# SCH_CLASS_ESP32-S2-MAIN_2024-03-08.net
KiCad netlist of a schematic drawn in EasyEDA
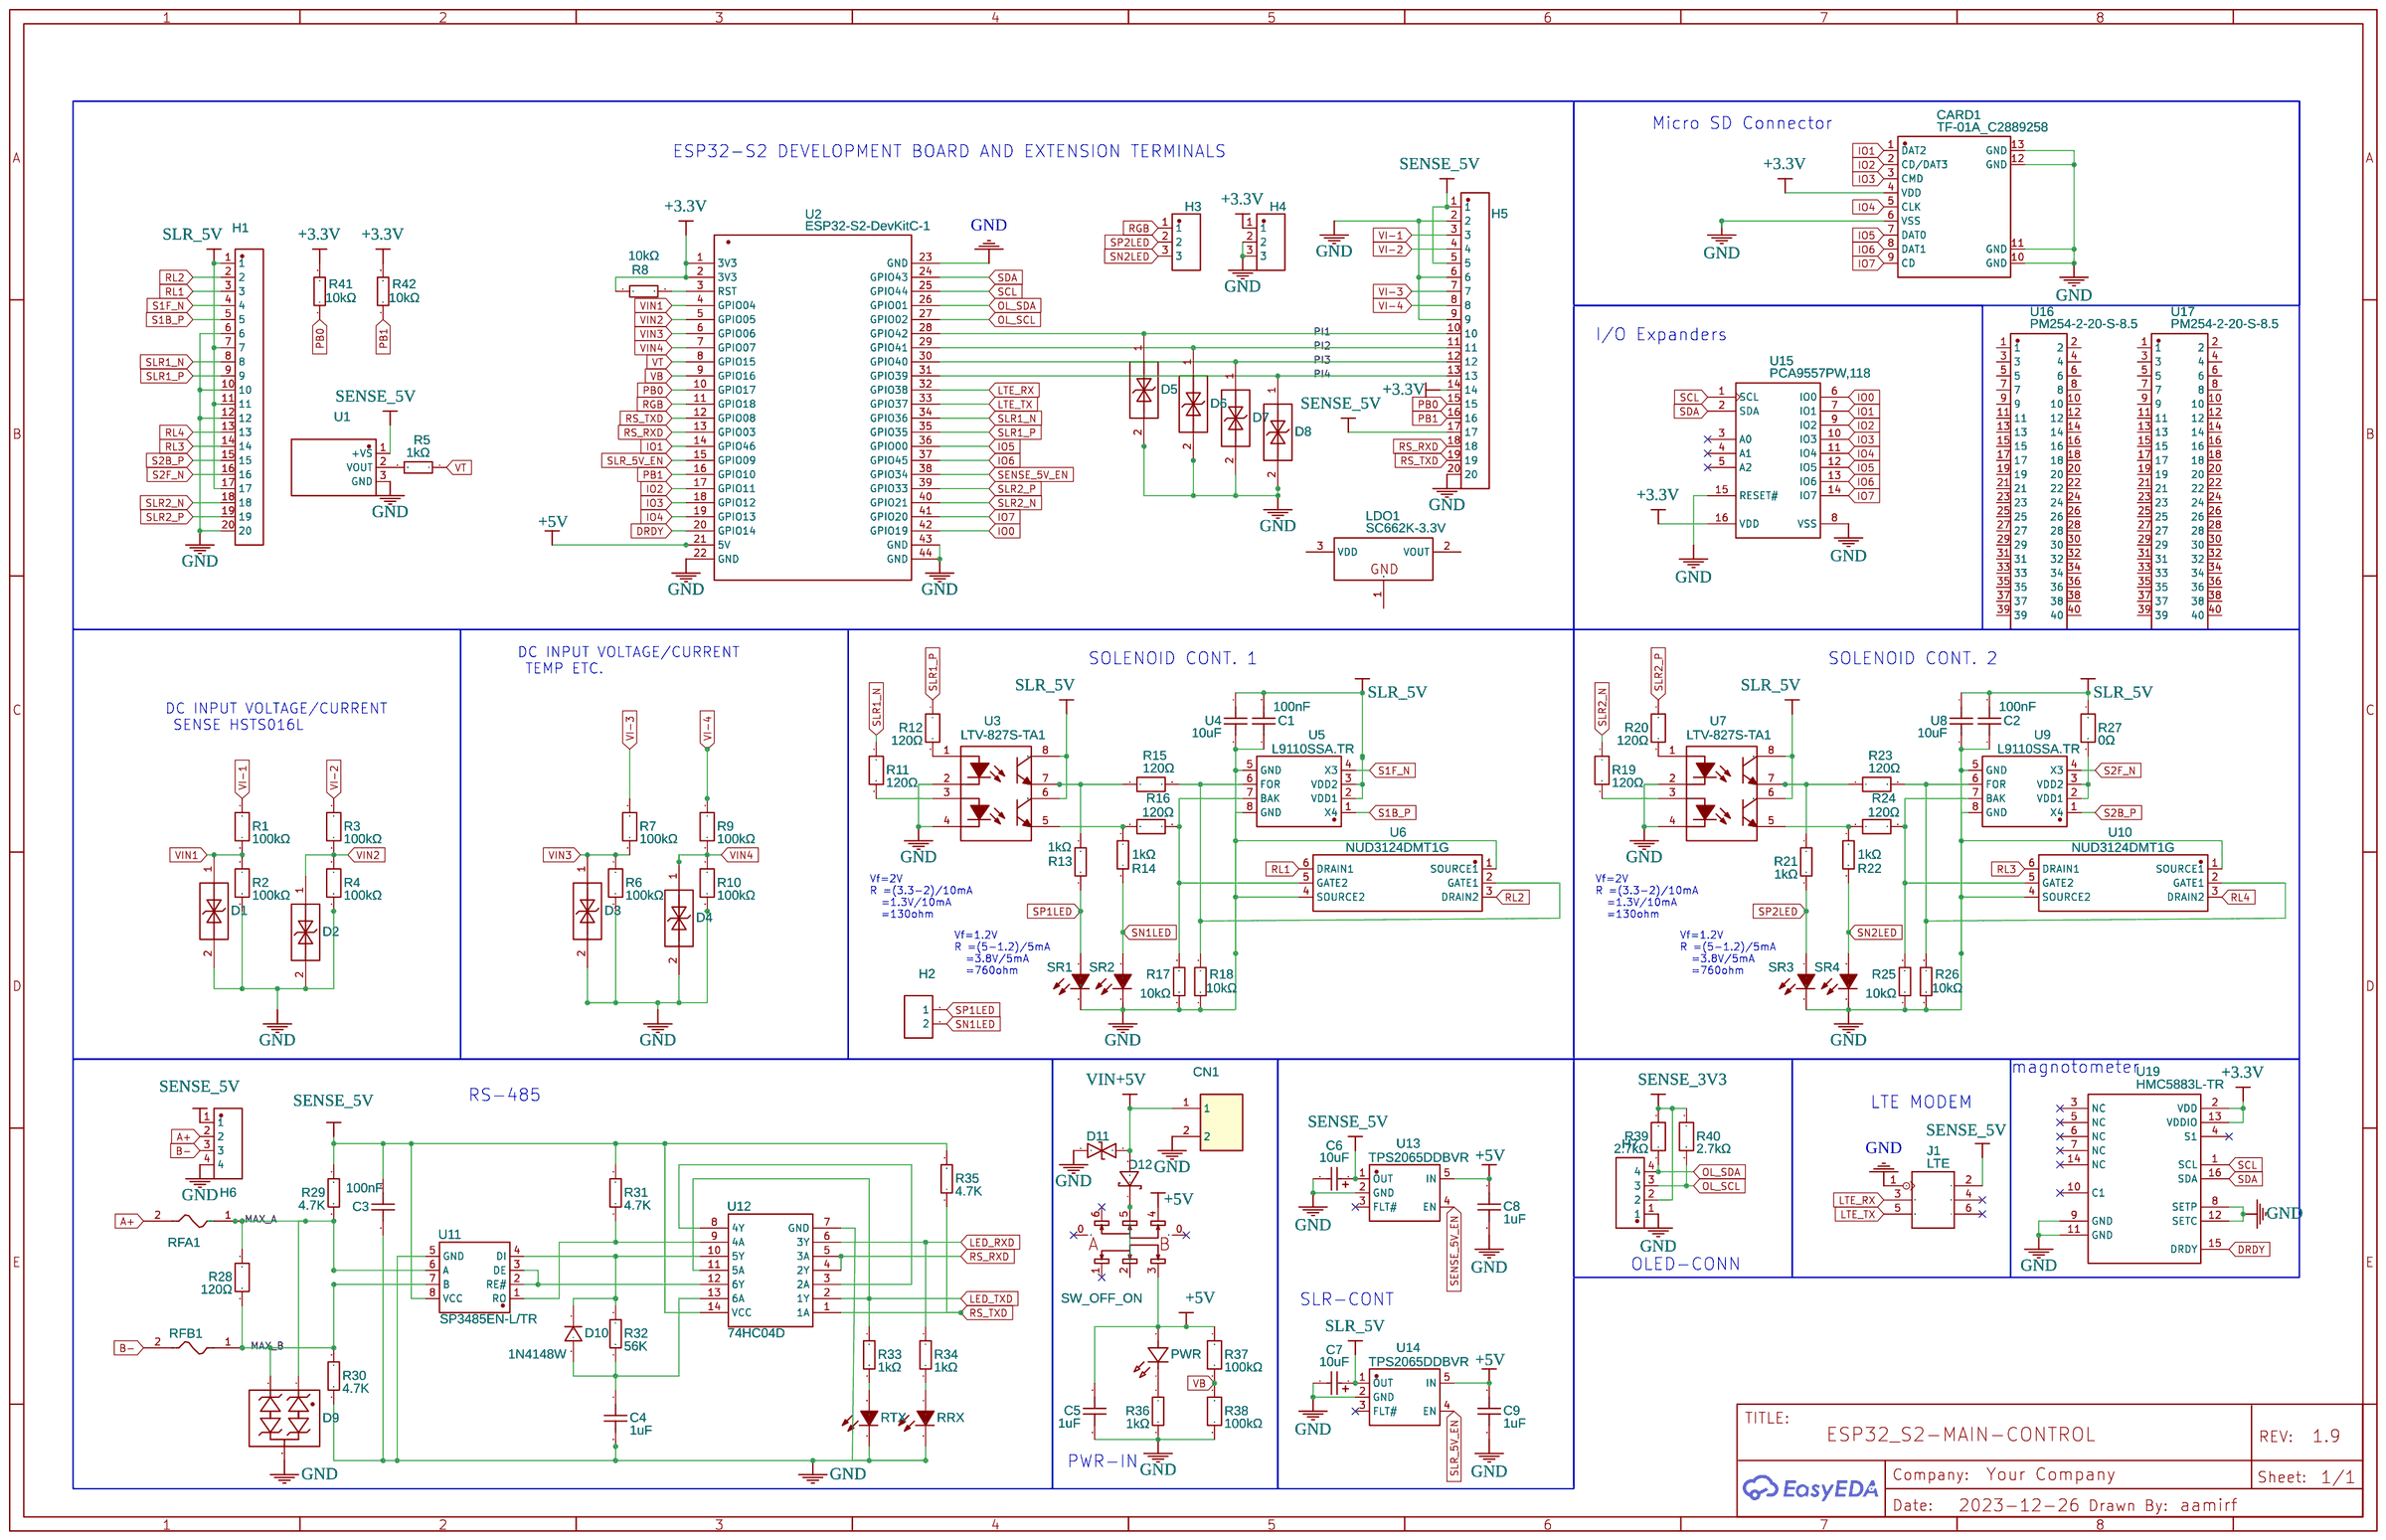
[diagram p0: schematic sheet]

(export (version "E")
  (design (tool "Eeschema 10.0.6"))
  (components
    (comp (ref "C1")
      (value "100nF")
      (fields (field (name "Manufacturer Part") "C1005X5R0J104K050BA") (field (name "Manufacturer") "TDK"))
      (libsource (lib "") (part "C1005X5R0J104K050BA"))
    )
    (comp (ref "C2")
      (value "100nF")
      (fields (field (name "Manufacturer Part") "C1005X5R0J104K050BA") (field (name "Manufacturer") "TDK"))
      (libsource (lib "") (part "C1005X5R0J104K050BA"))
    )
    (comp (ref "C3")
      (value "100nF")
      (fields (field (name "Manufacturer Part") "C1005X5R0J104K050BA") (field (name "Manufacturer") "TDK"))
      (libsource (lib "") (part "C1005X5R0J104K050BA_1"))
    )
    (comp (ref "C4")
      (value "1uF")
      (fields
        (field (name "Manufacturer Part") "GRM155R61H105ME05D")
        (field (name "Manufacturer") "muRata(村田)")
      )
      (libsource (lib "") (part "GRM155R61H105ME05D"))
    )
    (comp (ref "C5")
      (value "1uF")
      (fields
        (field (name "Manufacturer Part") "GRM155R61H105ME05D")
        (field (name "Manufacturer") "muRata(村田)")
      )
      (libsource (lib "") (part "GRM155R61H105ME05D_1"))
    )
    (comp (ref "C6")
      (value "10uF")
      (fields
        (field (name "Manufacturer Part") "CA45A-A-16V-10uF-K")
        (field (name "Manufacturer") "CEC(振华新云)")
      )
      (libsource (lib "") (part "CA45A-A-16V-10UF-K"))
    )
    (comp (ref "C7")
      (value "10uF")
      (fields
        (field (name "Manufacturer Part") "CA45A-A-16V-10uF-K")
        (field (name "Manufacturer") "CEC(振华新云)")
      )
      (libsource (lib "") (part "CA45A-A-16V-10UF-K"))
    )
    (comp (ref "C8")
      (value "1uF")
      (fields
        (field (name "Manufacturer Part") "GRM155R61H105ME05D")
        (field (name "Manufacturer") "muRata(村田)")
      )
      (libsource (lib "") (part "GRM155R61H105ME05D"))
    )
    (comp (ref "C9")
      (value "1uF")
      (fields
        (field (name "Manufacturer Part") "GRM155R61H105ME05D")
        (field (name "Manufacturer") "muRata(村田)")
      )
      (libsource (lib "") (part "GRM155R61H105ME05D"))
    )
    (comp (ref "CARD1")
      (value "TF-01A_C2889258")
      (fields (field (name "Manufacturer Part") "TF-01A") (field (name "Manufacturer") "Yuandi(台湾元迪)"))
      (libsource (lib "") (part "TF-01A_C2889258"))
    )
    (comp (ref "CN1")
      (value "B2B-PH-K-S(LF)(SN)")
      (fields (field (name "Manufacturer") "JST"))
      (libsource (lib "") (part "B2B-PH-K-S(LF)(SN)"))
    )
    (comp (ref "D1")
      (value "KESD5311X")
      (fields (field (name "Manufacturer") "KUU"))
      (libsource (lib "") (part "KESD5311X"))
    )
    (comp (ref "D2")
      (value "KESD5311X")
      (fields (field (name "Manufacturer") "KUU"))
      (libsource (lib "") (part "KESD5311X"))
    )
    (comp (ref "D3")
      (value "KESD5311X")
      (fields (field (name "Manufacturer") "KUU"))
      (libsource (lib "") (part "KESD5311X"))
    )
    (comp (ref "D4")
      (value "KESD5311X")
      (fields (field (name "Manufacturer") "KUU"))
      (libsource (lib "") (part "KESD5311X"))
    )
    (comp (ref "D5")
      (value "KESD5311X")
      (fields (field (name "Manufacturer") "KUU"))
      (libsource (lib "") (part "KESD5311X"))
    )
    (comp (ref "D6")
      (value "KESD5311X")
      (fields (field (name "Manufacturer") "KUU"))
      (libsource (lib "") (part "KESD5311X"))
    )
    (comp (ref "D7")
      (value "KESD5311X")
      (fields (field (name "Manufacturer") "KUU"))
      (libsource (lib "") (part "KESD5311X"))
    )
    (comp (ref "D8")
      (value "KESD5311X")
      (fields (field (name "Manufacturer") "KUU"))
      (libsource (lib "") (part "KESD5311X"))
    )
    (comp (ref "D9")
      (value "SM712_C502564")
      (fields (field (name "Manufacturer Part") "SM712") (field (name "Manufacturer") "MDD"))
      (libsource (lib "") (part "SM712_C502564"))
    )
    (comp (ref "D10")
      (value "1N4148W")
      (fields (field (name "Manufacturer") "SEMTECH"))
      (libsource (lib "") (part "1N4148W_C81598"))
    )
    (comp (ref "D11")
      (value "LESD5D5.0CT1G")
      (fields (field (name "Manufacturer") "LRC(乐山无线电)"))
      (libsource (lib "") (part "LESD5D5.0CT1G"))
    )
    (comp (ref "D12")
      (value "BAT760-7")
      (fields (field (name "Manufacturer") "DIODES(美台)"))
      (libsource (lib "") (part "BAT760-7"))
    )
    (comp (ref "H1")
      (value "KH-2.54PH180-1X20P-L11.5")
      (fields (field (name "Manufacturer") "kinghelm(金航标)"))
      (libsource (lib "") (part "KH-2.54PH180-1X20P-L11.5"))
    )
    (comp (ref "H2") (value "HDR-F-2.54_1x2") (libsource (lib "") (part "HDR-F-2.54_1x2")))
    (comp (ref "H3")
      (value "KH-2.54PH180-1X3P-L11.5")
      (fields (field (name "Manufacturer") "kinghelm(金航标)"))
      (libsource (lib "") (part "KH-2.54PH180-1X3P-L11.5"))
    )
    (comp (ref "H4")
      (value "KH-2.54PH180-1X3P-L11.5")
      (fields (field (name "Manufacturer") "kinghelm(金航标)"))
      (libsource (lib "") (part "KH-2.54PH180-1X3P-L11.5"))
    )
    (comp (ref "H5")
      (value "KH-2.54PH180-1X20P-L11.5")
      (fields (field (name "Manufacturer") "kinghelm(金航标)"))
      (libsource (lib "") (part "KH-2.54PH180-1X20P-L11.5"))
    )
    (comp (ref "H6")
      (value "X6511WV-04H-C30D60")
      (fields (field (name "Manufacturer") "XKB Connectivity(中国星坤)"))
      (libsource (lib "") (part "X6511WV-04H-C30D60"))
    )
    (comp (ref "H7")
      (value "X6511WV-04H-C30D60")
      (fields (field (name "Manufacturer") "XKB Connectivity(中国星坤)"))
      (libsource (lib "") (part "X6511WV-04H-C30D60_1"))
    )
    (comp (ref "J1") (value "LTE") (libsource (lib "") (part "MALE-HEADER(2X3P-2.54)")))
    (comp (ref "LDO1")
      (value "SC662K-3.3V")
      (fields (field (name "Manufacturer") "FM(富满)"))
      (libsource (lib "") (part "SC662K-3.3V"))
    )
    (comp (ref "PWR")
      (value "16-213/BHC-ZL1M2B6Y/3T")
      (fields (field (name "Manufacturer") "EVERLIGHT(亿光)"))
      (libsource (lib "") (part "16-213/BHC-ZL1M2B6Y/3T"))
    )
    (comp (ref "R1")
      (value "100kΩ")
      (fields
        (field (name "Manufacturer Part") "CQ02WGJ0104TCE")
        (field (name "Manufacturer") "UNI-ROYAL(厚声)")
      )
      (libsource (lib "") (part "CQ02WGJ0104TCE"))
    )
    (comp (ref "R2")
      (value "100kΩ")
      (fields
        (field (name "Manufacturer Part") "CQ02WGJ0104TCE")
        (field (name "Manufacturer") "UNI-ROYAL(厚声)")
      )
      (libsource (lib "") (part "CQ02WGJ0104TCE"))
    )
    (comp (ref "R3")
      (value "100kΩ")
      (fields
        (field (name "Manufacturer Part") "CQ02WGJ0104TCE")
        (field (name "Manufacturer") "UNI-ROYAL(厚声)")
      )
      (libsource (lib "") (part "CQ02WGJ0104TCE"))
    )
    (comp (ref "R4")
      (value "100kΩ")
      (fields
        (field (name "Manufacturer Part") "CQ02WGJ0104TCE")
        (field (name "Manufacturer") "UNI-ROYAL(厚声)")
      )
      (libsource (lib "") (part "CQ02WGJ0104TCE"))
    )
    (comp (ref "R5")
      (value "1kΩ")
      (fields (field (name "Manufacturer Part") "AR02DTD1001") (field (name "Manufacturer") "Viking(光颉)"))
      (libsource (lib "") (part "AR02DTD1001"))
    )
    (comp (ref "R6")
      (value "100kΩ")
      (fields
        (field (name "Manufacturer Part") "CQ02WGJ0104TCE")
        (field (name "Manufacturer") "UNI-ROYAL(厚声)")
      )
      (libsource (lib "") (part "CQ02WGJ0104TCE"))
    )
    (comp (ref "R7")
      (value "100kΩ")
      (fields
        (field (name "Manufacturer Part") "CQ02WGJ0104TCE")
        (field (name "Manufacturer") "UNI-ROYAL(厚声)")
      )
      (libsource (lib "") (part "CQ02WGJ0104TCE"))
    )
    (comp (ref "R8")
      (value "10kΩ")
      (fields
        (field (name "Manufacturer Part") "0402WGF1002TCE")
        (field (name "Manufacturer") "UNI-ROYAL(厚声)")
      )
      (libsource (lib "") (part "0402WGF1002TCE_1"))
    )
    (comp (ref "R9")
      (value "100kΩ")
      (fields
        (field (name "Manufacturer Part") "CQ02WGJ0104TCE")
        (field (name "Manufacturer") "UNI-ROYAL(厚声)")
      )
      (libsource (lib "") (part "CQ02WGJ0104TCE"))
    )
    (comp (ref "R10")
      (value "100kΩ")
      (fields
        (field (name "Manufacturer Part") "CQ02WGJ0104TCE")
        (field (name "Manufacturer") "UNI-ROYAL(厚声)")
      )
      (libsource (lib "") (part "CQ02WGJ0104TCE"))
    )
    (comp (ref "R11")
      (value "120Ω")
      (fields (field (name "Manufacturer Part") "RM04FTN1200") (field (name "Manufacturer") "大毅科技"))
      (libsource (lib "") (part "RM04FTN1200"))
    )
    (comp (ref "R12")
      (value "120Ω")
      (fields (field (name "Manufacturer Part") "RM04FTN1200") (field (name "Manufacturer") "大毅科技"))
      (libsource (lib "") (part "RM04FTN1200"))
    )
    (comp (ref "R13")
      (value "1kΩ")
      (fields (field (name "Manufacturer Part") "AR02DTD1001") (field (name "Manufacturer") "Viking(光颉)"))
      (libsource (lib "") (part "AR02DTD1001_1"))
    )
    (comp (ref "R14")
      (value "1kΩ")
      (fields (field (name "Manufacturer Part") "AR02DTD1001") (field (name "Manufacturer") "Viking(光颉)"))
      (libsource (lib "") (part "AR02DTD1001_1"))
    )
    (comp (ref "R15")
      (value "120Ω")
      (fields (field (name "Manufacturer Part") "RM04FTN1200") (field (name "Manufacturer") "大毅科技"))
      (libsource (lib "") (part "RM04FTN1200_1"))
    )
    (comp (ref "R16")
      (value "120Ω")
      (fields (field (name "Manufacturer Part") "RM04FTN1200") (field (name "Manufacturer") "大毅科技"))
      (libsource (lib "") (part "RM04FTN1200_1"))
    )
    (comp (ref "R17")
      (value "10kΩ")
      (fields
        (field (name "Manufacturer Part") "0402WGF1002TCE")
        (field (name "Manufacturer") "UNI-ROYAL(厚声)")
      )
      (libsource (lib "") (part "0402WGF1002TCE"))
    )
    (comp (ref "R18")
      (value "10kΩ")
      (fields
        (field (name "Manufacturer Part") "0402WGF1002TCE")
        (field (name "Manufacturer") "UNI-ROYAL(厚声)")
      )
      (libsource (lib "") (part "0402WGF1002TCE"))
    )
    (comp (ref "R19")
      (value "120Ω")
      (fields (field (name "Manufacturer Part") "RM04FTN1200") (field (name "Manufacturer") "大毅科技"))
      (libsource (lib "") (part "RM04FTN1200"))
    )
    (comp (ref "R20")
      (value "120Ω")
      (fields (field (name "Manufacturer Part") "RM04FTN1200") (field (name "Manufacturer") "大毅科技"))
      (libsource (lib "") (part "RM04FTN1200"))
    )
    (comp (ref "R21")
      (value "1kΩ")
      (fields (field (name "Manufacturer Part") "AR02DTD1001") (field (name "Manufacturer") "Viking(光颉)"))
      (libsource (lib "") (part "AR02DTD1001_1"))
    )
    (comp (ref "R22")
      (value "1kΩ")
      (fields (field (name "Manufacturer Part") "AR02DTD1001") (field (name "Manufacturer") "Viking(光颉)"))
      (libsource (lib "") (part "AR02DTD1001_1"))
    )
    (comp (ref "R23")
      (value "120Ω")
      (fields (field (name "Manufacturer Part") "RM04FTN1200") (field (name "Manufacturer") "大毅科技"))
      (libsource (lib "") (part "RM04FTN1200_1"))
    )
    (comp (ref "R24")
      (value "120Ω")
      (fields (field (name "Manufacturer Part") "RM04FTN1200") (field (name "Manufacturer") "大毅科技"))
      (libsource (lib "") (part "RM04FTN1200_1"))
    )
    (comp (ref "R25")
      (value "10kΩ")
      (fields
        (field (name "Manufacturer Part") "0402WGF1002TCE")
        (field (name "Manufacturer") "UNI-ROYAL(厚声)")
      )
      (libsource (lib "") (part "0402WGF1002TCE"))
    )
    (comp (ref "R26")
      (value "10kΩ")
      (fields
        (field (name "Manufacturer Part") "0402WGF1002TCE")
        (field (name "Manufacturer") "UNI-ROYAL(厚声)")
      )
      (libsource (lib "") (part "0402WGF1002TCE"))
    )
    (comp (ref "R27")
      (value "0Ω")
      (fields (field (name "Manufacturer Part") "CR-03JA7----0R") (field (name "Manufacturer") "Viking(光颉)"))
      (libsource (lib "") (part "CR-03JA7----0R"))
    )
    (comp (ref "R28")
      (value "120Ω")
      (fields (field (name "Manufacturer Part") "FRC0603J121 TS") (field (name "Manufacturer") "FOJAN(富捷)"))
      (libsource (lib "") (part "FRC0603J121 TS"))
    )
    (comp (ref "R29")
      (value "4.7K")
      (fields (field (name "Manufacturer Part") "0603WAF4701T5E") (field (name "Manufacturer") "UniOhm"))
      (libsource (lib "") (part "0603WAF4701T5E"))
    )
    (comp (ref "R30")
      (value "4.7K")
      (fields (field (name "Manufacturer Part") "0603WAF4701T5E") (field (name "Manufacturer") "UniOhm"))
      (libsource (lib "") (part "0603WAF4701T5E"))
    )
    (comp (ref "R31")
      (value "4.7K")
      (fields (field (name "Manufacturer Part") "0603WAF4701T5E") (field (name "Manufacturer") "UniOhm"))
      (libsource (lib "") (part "0603WAF4701T5E"))
    )
    (comp (ref "R32")
      (value "56K")
      (fields (field (name "Manufacturer Part") "0603WAF5602T5E") (field (name "Manufacturer") "UniOhm"))
      (libsource (lib "") (part "0603WAF5602T5E"))
    )
    (comp (ref "R33")
      (value "1kΩ")
      (fields (field (name "Manufacturer Part") "AR02DTD1001") (field (name "Manufacturer") "Viking(光颉)"))
      (libsource (lib "") (part "AR02DTD1001_1"))
    )
    (comp (ref "R34")
      (value "1kΩ")
      (fields (field (name "Manufacturer Part") "AR02DTD1001") (field (name "Manufacturer") "Viking(光颉)"))
      (libsource (lib "") (part "AR02DTD1001_1"))
    )
    (comp (ref "R35")
      (value "4.7K")
      (fields (field (name "Manufacturer Part") "0603WAF4701T5E") (field (name "Manufacturer") "UniOhm"))
      (libsource (lib "") (part "0603WAF4701T5E"))
    )
    (comp (ref "R36")
      (value "1kΩ")
      (fields (field (name "Manufacturer Part") "AR02DTD1001") (field (name "Manufacturer") "Viking(光颉)"))
      (libsource (lib "") (part "AR02DTD1001_1"))
    )
    (comp (ref "R37")
      (value "100kΩ")
      (fields
        (field (name "Manufacturer Part") "CQ02WGJ0104TCE")
        (field (name "Manufacturer") "UNI-ROYAL(厚声)")
      )
      (libsource (lib "") (part "CQ02WGJ0104TCE"))
    )
    (comp (ref "R38")
      (value "100kΩ")
      (fields
        (field (name "Manufacturer Part") "CQ02WGJ0104TCE")
        (field (name "Manufacturer") "UNI-ROYAL(厚声)")
      )
      (libsource (lib "") (part "CQ02WGJ0104TCE"))
    )
    (comp (ref "R39")
      (value "2.7kΩ")
      (fields (field (name "Manufacturer Part") "CR-02FL6---2K7") (field (name "Manufacturer") "Viking(光颉)"))
      (libsource (lib "") (part "CR-02FL6---2K7"))
    )
    (comp (ref "R40")
      (value "2.7kΩ")
      (fields (field (name "Manufacturer Part") "CR-02FL6---2K7") (field (name "Manufacturer") "Viking(光颉)"))
      (libsource (lib "") (part "CR-02FL6---2K7"))
    )
    (comp (ref "R41")
      (value "10kΩ")
      (fields
        (field (name "Manufacturer Part") "0402WGF1002TCE")
        (field (name "Manufacturer") "UNI-ROYAL(厚声)")
      )
      (libsource (lib "") (part "0402WGF1002TCE"))
    )
    (comp (ref "R42")
      (value "10kΩ")
      (fields
        (field (name "Manufacturer Part") "0402WGF1002TCE")
        (field (name "Manufacturer") "UNI-ROYAL(厚声)")
      )
      (libsource (lib "") (part "0402WGF1002TCE"))
    )
    (comp (ref "RFA1")
      (value "MF-MSMF010-2")
      (fields (field (name "Manufacturer") "BOURNS"))
      (libsource (lib "") (part "MF-MSMF010-2_1"))
    )
    (comp (ref "RFB1")
      (value "MF-MSMF010-2")
      (fields (field (name "Manufacturer") "BOURNS"))
      (libsource (lib "") (part "MF-MSMF010-2"))
    )
    (comp (ref "RRX")
      (value "16-213/GHC-YR1S1/3T")
      (fields (field (name "Manufacturer") "EVERLIGHT(亿光)"))
      (libsource (lib "") (part "16-213/GHC-YR1S1/3T"))
    )
    (comp (ref "RTX")
      (value "16-213/SDRC/S530-A3/TR8")
      (fields
        (field (name "Manufacturer Part") "16-213SDRC/S530-A3/TR8")
        (field (name "Manufacturer") "EVERLIGHT(亿光)")
      )
      (libsource (lib "") (part "16-213/SDRC/S530-A3/TR8_1"))
    )
    (comp (ref "SR1")
      (value "16-213/GHC-YR1S1/3T")
      (fields (field (name "Manufacturer") "EVERLIGHT(亿光)"))
      (libsource (lib "") (part "16-213/GHC-YR1S1/3T_1"))
    )
    (comp (ref "SR2")
      (value "16-213/SDRC/S530-A3/TR8")
      (fields
        (field (name "Manufacturer Part") "16-213SDRC/S530-A3/TR8")
        (field (name "Manufacturer") "EVERLIGHT(亿光)")
      )
      (libsource (lib "") (part "16-213/SDRC/S530-A3/TR8"))
    )
    (comp (ref "SR3")
      (value "16-213/GHC-YR1S1/3T")
      (fields (field (name "Manufacturer") "EVERLIGHT(亿光)"))
      (libsource (lib "") (part "16-213/GHC-YR1S1/3T_1"))
    )
    (comp (ref "SR4")
      (value "16-213/SDRC/S530-A3/TR8")
      (fields
        (field (name "Manufacturer Part") "16-213SDRC/S530-A3/TR8")
        (field (name "Manufacturer") "EVERLIGHT(亿光)")
      )
      (libsource (lib "") (part "16-213/SDRC/S530-A3/TR8"))
    )
    (comp (ref "SW1")
      (value "SW_OFF_ON")
      (fields (field (name "Manufacturer Part") "TA-3519S-A1") (field (name "Manufacturer") "Yuandi(元迪)"))
      (libsource (lib "") (part "TA-3519S-A1"))
    )
    (comp (ref "U1")
      (value "LM35DZ/LFT1")
      (fields (field (name "Manufacturer") "TI(德州仪器)"))
      (libsource (lib "") (part "LM35DZ/LFT1"))
    )
    (comp (ref "U2")
      (value "ESP32-S2-DevKitC-1")
      (fields (field (name "Manufacturer") "Espressif Manifacturer"))
      (libsource (lib "") (part "ESP32-S2-DevKitC-1"))
    )
    (comp (ref "U3")
      (value "LTV-827S-TA1")
      (fields (field (name "Manufacturer") "LITEON"))
      (libsource (lib "") (part "Unknown_-2500_-870"))
    )
    (comp (ref "U4")
      (value "10uF")
      (fields (field (name "Manufacturer Part") "CGB3C1JB0J106M065AC") (field (name "Manufacturer") "TDK"))
      (libsource (lib "") (part "CGB3C1JB0J106M065AC"))
    )
    (comp (ref "U5")
      (value "L9110SSA.TR")
      (fields (field (name "Manufacturer") "I-CORE(中微爱芯)"))
      (libsource (lib "") (part "L9110SSA.TR"))
    )
    (comp (ref "U6")
      (value "NUD3124DMT1G")
      (fields (field (name "Manufacturer") "ON Semicon"))
      (libsource (lib "") (part "NUD3124DMT1G"))
    )
    (comp (ref "U7")
      (value "LTV-827S-TA1")
      (fields (field (name "Manufacturer") "LITEON"))
      (libsource (lib "") (part "Unknown_-1985_-870"))
    )
    (comp (ref "U8")
      (value "10uF")
      (fields (field (name "Manufacturer Part") "CGB3C1JB0J106M065AC") (field (name "Manufacturer") "TDK"))
      (libsource (lib "") (part "CGB3C1JB0J106M065AC"))
    )
    (comp (ref "U9")
      (value "L9110SSA.TR")
      (fields (field (name "Manufacturer") "I-CORE(中微爱芯)"))
      (libsource (lib "") (part "L9110SSA.TR"))
    )
    (comp (ref "U10")
      (value "NUD3124DMT1G")
      (fields (field (name "Manufacturer") "ON Semicon"))
      (libsource (lib "") (part "NUD3124DMT1G"))
    )
    (comp (ref "U11")
      (value "SP3485EN-L/TR")
      (fields (field (name "Manufacturer") "EXAR"))
      (libsource (lib "") (part "SP3485EN-L/TR"))
    )
    (comp (ref "U12")
      (value "74HC04D")
      (fields (field (name "Manufacturer Part") "74HC04D,653") (field (name "Manufacturer") "Nexperia"))
      (libsource (lib "") (part "Unknown_-2665_-535"))
    )
    (comp (ref "U13")
      (value "TPS2065DDBVR")
      (fields (field (name "Manufacturer") "TI(德州仪器)"))
      (libsource (lib "") (part "TPS2065DDBVR"))
    )
    (comp (ref "U14")
      (value "TPS2065DDBVR")
      (fields (field (name "Manufacturer") "TI(德州仪器)"))
      (libsource (lib "") (part "TPS2065DDBVR"))
    )
    (comp (ref "U15")
      (value "PCA9557PW,118")
      (fields (field (name "Manufacturer") "NXP(恩智浦)"))
      (libsource (lib "") (part "PCA9557PW,118"))
    )
    (comp (ref "U16")
      (value "PM254-2-20-S-8.5")
      (fields (field (name "Manufacturer") "HCTL(华灿天禄)"))
      (libsource (lib "") (part "PM254-2-20-S-8.5"))
    )
    (comp (ref "U17")
      (value "PM254-2-20-S-8.5")
      (fields (field (name "Manufacturer") "HCTL(华灿天禄)"))
      (libsource (lib "") (part "PM254-2-20-S-8.5"))
    )
    (comp (ref "U19") (value "HMC5883L-TR") (libsource (lib "") (part "HMC5883L-TR")))
  )
  (nets
    (net (code "1") (name "+3.3V") (class "Default")
      (node (ref "CARD1") (pin "4") (pinfunction "VDD_4") (pintype "unspecified"))
      (node (ref "H4") (pin "1") (pinfunction "1_1") (pintype "unspecified"))
      (node (ref "H5") (pin "14") (pinfunction "14_14") (pintype "unspecified"))
      (node (ref "R41") (pin "2") (pinfunction "2_2") (pintype "input"))
      (node (ref "R42") (pin "2") (pinfunction "2_2") (pintype "input"))
      (node (ref "R8") (pin "1") (pinfunction "1_1") (pintype "input"))
      (node (ref "U15") (pin "16") (pinfunction "VDD_16") (pintype "passive"))
      (node (ref "U19") (pin "13") (pinfunction "VDDIO_13") (pintype "unspecified"))
      (node (ref "U19") (pin "2") (pinfunction "VDD_2") (pintype "unspecified"))
      (node (ref "U2") (pin "1") (pinfunction "3V3_1") (pintype "passive"))
      (node (ref "U2") (pin "2") (pinfunction "3V3_2") (pintype "passive"))
    )
    (net (code "2") (name "+5V") (class "Default")
      (node (ref "C5") (pin "1") (pinfunction "1_1") (pintype "unspecified"))
      (node (ref "C8") (pin "1") (pinfunction "1_1") (pintype "unspecified"))
      (node (ref "C9") (pin "1") (pinfunction "1_1") (pintype "unspecified"))
      (node (ref "PWR") (pin "2") (pinfunction "A_2") (pintype "unspecified"))
      (node (ref "R37") (pin "1") (pinfunction "1_1") (pintype "unspecified"))
      (node (ref "SW1") (pin "3") (pinfunction "3_3") (pintype "unspecified"))
      (node (ref "SW1") (pin "4") (pinfunction "4_4") (pintype "unspecified"))
      (node (ref "U13") (pin "5") (pinfunction "IN_5") (pintype "unspecified"))
      (node (ref "U14") (pin "5") (pinfunction "IN_5") (pintype "unspecified"))
      (node (ref "U2") (pin "21") (pinfunction "5V_21") (pintype "passive"))
    )
    (net (code "3") (name "/MAX_A") (class "Default")
      (node (ref "D9") (pin "1") (pinfunction "1_1") (pintype "unspecified"))
      (node (ref "R28") (pin "1") (pinfunction "1_1") (pintype "unspecified"))
      (node (ref "R29") (pin "1") (pinfunction "1_1") (pintype "input"))
      (node (ref "RFA1") (pin "1") (pinfunction "1_1") (pintype "unspecified"))
      (node (ref "U11") (pin "6") (pinfunction "A_6") (pintype "unspecified"))
    )
    (net (code "4") (name "/MAX_B") (class "Default")
      (node (ref "D9") (pin "2") (pinfunction "2_2") (pintype "unspecified"))
      (node (ref "R28") (pin "2") (pinfunction "2_2") (pintype "unspecified"))
      (node (ref "R30") (pin "2") (pinfunction "2_2") (pintype "input"))
      (node (ref "RFB1") (pin "1") (pinfunction "1_1") (pintype "unspecified"))
      (node (ref "U11") (pin "7") (pinfunction "B_7") (pintype "unspecified"))
    )
    (net (code "5") (name "/PI1") (class "Default")
      (node (ref "D5") (pin "1") (pinfunction "1_1") (pintype "unspecified"))
      (node (ref "H5") (pin "10") (pinfunction "10_10") (pintype "unspecified"))
      (node (ref "U2") (pin "28") (pinfunction "GPIO42_28") (pintype "bidirectional"))
    )
    (net (code "6") (name "/PI2") (class "Default")
      (node (ref "D6") (pin "1") (pinfunction "1_1") (pintype "unspecified"))
      (node (ref "H5") (pin "11") (pinfunction "11_11") (pintype "unspecified"))
      (node (ref "U2") (pin "29") (pinfunction "GPIO41_29") (pintype "bidirectional"))
    )
    (net (code "7") (name "/PI3") (class "Default")
      (node (ref "D7") (pin "1") (pinfunction "1_1") (pintype "unspecified"))
      (node (ref "H5") (pin "12") (pinfunction "12_12") (pintype "unspecified"))
      (node (ref "U2") (pin "30") (pinfunction "GPIO40_30") (pintype "bidirectional"))
    )
    (net (code "8") (name "/PI4") (class "Default")
      (node (ref "D8") (pin "1") (pinfunction "1_1") (pintype "unspecified"))
      (node (ref "H5") (pin "13") (pinfunction "13_13") (pintype "unspecified"))
      (node (ref "U2") (pin "31") (pinfunction "GPIO39_31") (pintype "bidirectional"))
    )
    (net (code "9") (name "A+") (class "Default")
      (node (ref "H6") (pin "2") (pinfunction "2_2") (pintype "unspecified"))
      (node (ref "RFA1") (pin "2") (pinfunction "2_2") (pintype "unspecified"))
    )
    (net (code "10") (name "B-") (class "Default")
      (node (ref "H6") (pin "3") (pinfunction "3_3") (pintype "unspecified"))
      (node (ref "RFB1") (pin "2") (pinfunction "2_2") (pintype "unspecified"))
    )
    (net (code "11") (name "DRDY") (class "Default")
      (node (ref "U19") (pin "15") (pinfunction "DRDY_15") (pintype "unspecified"))
      (node (ref "U2") (pin "20") (pinfunction "GPIO14_20") (pintype "bidirectional"))
    )
    (net (code "12") (name "GND") (class "Default")
      (node (ref "C1") (pin "1") (pinfunction "1_1") (pintype "unspecified"))
      (node (ref "C2") (pin "1") (pinfunction "1_1") (pintype "unspecified"))
      (node (ref "C3") (pin "1") (pinfunction "1_1") (pintype "unspecified"))
      (node (ref "C4") (pin "2") (pinfunction "2_2") (pintype "unspecified"))
      (node (ref "C5") (pin "2") (pinfunction "2_2") (pintype "unspecified"))
      (node (ref "C6") (pin "2") (pinfunction "2_2") (pintype "input"))
      (node (ref "C7") (pin "2") (pinfunction "2_2") (pintype "input"))
      (node (ref "C8") (pin "2") (pinfunction "2_2") (pintype "unspecified"))
      (node (ref "C9") (pin "2") (pinfunction "2_2") (pintype "unspecified"))
      (node (ref "CARD1") (pin "10") (pinfunction "GND_10") (pintype "unspecified"))
      (node (ref "CARD1") (pin "11") (pinfunction "GND_11") (pintype "unspecified"))
      (node (ref "CARD1") (pin "12") (pinfunction "GND_12") (pintype "unspecified"))
      (node (ref "CARD1") (pin "13") (pinfunction "GND_13") (pintype "unspecified"))
      (node (ref "CARD1") (pin "6") (pinfunction "VSS_6") (pintype "unspecified"))
      (node (ref "CN1") (pin "2") (pinfunction "2_2") (pintype "input"))
      (node (ref "D1") (pin "2") (pinfunction "2_2") (pintype "unspecified"))
      (node (ref "D11") (pin "1") (pinfunction "1_1") (pintype "unspecified"))
      (node (ref "D2") (pin "2") (pinfunction "2_2") (pintype "unspecified"))
      (node (ref "D3") (pin "2") (pinfunction "2_2") (pintype "unspecified"))
      (node (ref "D4") (pin "2") (pinfunction "2_2") (pintype "unspecified"))
      (node (ref "D5") (pin "2") (pinfunction "2_2") (pintype "unspecified"))
      (node (ref "D6") (pin "2") (pinfunction "2_2") (pintype "unspecified"))
      (node (ref "D7") (pin "2") (pinfunction "2_2") (pintype "unspecified"))
      (node (ref "D8") (pin "2") (pinfunction "2_2") (pintype "unspecified"))
      (node (ref "D9") (pin "3") (pinfunction "3_3") (pintype "unspecified"))
      (node (ref "H1") (pin "10") (pinfunction "10_10") (pintype "unspecified"))
      (node (ref "H1") (pin "12") (pinfunction "12_12") (pintype "unspecified"))
      (node (ref "H1") (pin "20") (pinfunction "20_20") (pintype "unspecified"))
      (node (ref "H1") (pin "6") (pinfunction "6_6") (pintype "unspecified"))
      (node (ref "H4") (pin "2") (pinfunction "2_2") (pintype "unspecified"))
      (node (ref "H4") (pin "3") (pinfunction "3_3") (pintype "unspecified"))
      (node (ref "H5") (pin "2") (pinfunction "2_2") (pintype "unspecified"))
      (node (ref "H5") (pin "20") (pinfunction "20_20") (pintype "unspecified"))
      (node (ref "H5") (pin "6") (pinfunction "6_6") (pintype "unspecified"))
      (node (ref "H5") (pin "9") (pinfunction "9_9") (pintype "unspecified"))
      (node (ref "H6") (pin "4") (pinfunction "4_4") (pintype "unspecified"))
      (node (ref "H7") (pin "1") (pinfunction "1_1") (pintype "unspecified"))
      (node (ref "J1") (pin "1") (pinfunction "1_1") (pintype "bidirectional"))
      (node (ref "R10") (pin "2") (pinfunction "2_2") (pintype "unspecified"))
      (node (ref "R17") (pin "1") (pinfunction "1_1") (pintype "input"))
      (node (ref "R18") (pin "1") (pinfunction "1_1") (pintype "input"))
      (node (ref "R2") (pin "2") (pinfunction "2_2") (pintype "unspecified"))
      (node (ref "R25") (pin "1") (pinfunction "1_1") (pintype "input"))
      (node (ref "R26") (pin "1") (pinfunction "1_1") (pintype "input"))
      (node (ref "R30") (pin "1") (pinfunction "1_1") (pintype "input"))
      (node (ref "R36") (pin "2") (pinfunction "2_2") (pintype "unspecified"))
      (node (ref "R38") (pin "2") (pinfunction "2_2") (pintype "unspecified"))
      (node (ref "R4") (pin "2") (pinfunction "2_2") (pintype "unspecified"))
      (node (ref "R6") (pin "2") (pinfunction "2_2") (pintype "unspecified"))
      (node (ref "RRX") (pin "2") (pinfunction "C_2") (pintype "input"))
      (node (ref "RTX") (pin "1") (pinfunction "-_1") (pintype "input"))
      (node (ref "SR1") (pin "2") (pinfunction "C_2") (pintype "input"))
      (node (ref "SR2") (pin "1") (pinfunction "-_1") (pintype "input"))
      (node (ref "SR3") (pin "2") (pinfunction "C_2") (pintype "input"))
      (node (ref "SR4") (pin "1") (pinfunction "-_1") (pintype "input"))
      (node (ref "U1") (pin "3") (pinfunction "GND_3") (pintype "unspecified"))
      (node (ref "U10") (pin "1") (pinfunction "SOURCE1_1") (pintype "unspecified"))
      (node (ref "U10") (pin "4") (pinfunction "SOURCE2_4") (pintype "unspecified"))
      (node (ref "U11") (pin "5") (pinfunction "GND_5") (pintype "unspecified"))
      (node (ref "U12") (pin "7") (pinfunction "GND_7") (pintype "unspecified"))
      (node (ref "U13") (pin "2") (pinfunction "GND_2") (pintype "unspecified"))
      (node (ref "U14") (pin "2") (pinfunction "GND_2") (pintype "unspecified"))
      (node (ref "U15") (pin "15") (pinfunction "RESET#_15") (pintype "unspecified"))
      (node (ref "U15") (pin "8") (pinfunction "VSS_8") (pintype "passive"))
      (node (ref "U19") (pin "11") (pinfunction "GND_11") (pintype "unspecified"))
      (node (ref "U19") (pin "12") (pinfunction "SETC_12") (pintype "unspecified"))
      (node (ref "U19") (pin "8") (pinfunction "SETP_8") (pintype "unspecified"))
      (node (ref "U19") (pin "9") (pinfunction "GND_9") (pintype "unspecified"))
      (node (ref "U2") (pin "22") (pinfunction "GND_22") (pintype "passive"))
      (node (ref "U2") (pin "23") (pinfunction "GND_23") (pintype "passive"))
      (node (ref "U2") (pin "43") (pinfunction "GND_43") (pintype "passive"))
      (node (ref "U2") (pin "44") (pinfunction "GND_44") (pintype "passive"))
      (node (ref "U3") (pin "2") (pinfunction "2_2") (pintype "unspecified"))
      (node (ref "U3") (pin "4") (pinfunction "4_4") (pintype "unspecified"))
      (node (ref "U4") (pin "2") (pinfunction "2_2") (pintype "unspecified"))
      (node (ref "U5") (pin "5") (pinfunction "GND_5") (pintype "unspecified"))
      (node (ref "U5") (pin "8") (pinfunction "GND_8") (pintype "unspecified"))
      (node (ref "U6") (pin "1") (pinfunction "SOURCE1_1") (pintype "unspecified"))
      (node (ref "U6") (pin "4") (pinfunction "SOURCE2_4") (pintype "unspecified"))
      (node (ref "U7") (pin "2") (pinfunction "2_2") (pintype "unspecified"))
      (node (ref "U7") (pin "4") (pinfunction "4_4") (pintype "unspecified"))
      (node (ref "U8") (pin "2") (pinfunction "2_2") (pintype "unspecified"))
      (node (ref "U9") (pin "5") (pinfunction "GND_5") (pintype "unspecified"))
      (node (ref "U9") (pin "8") (pinfunction "GND_8") (pintype "unspecified"))
    )
    (net (code "13") (name "IO0") (class "Default")
      (node (ref "U15") (pin "6") (pinfunction "IO0_6") (pintype "bidirectional"))
      (node (ref "U2") (pin "42") (pinfunction "GPIO19_42") (pintype "bidirectional"))
    )
    (net (code "14") (name "IO1") (class "Default")
      (node (ref "CARD1") (pin "1") (pinfunction "DAT2_1") (pintype "unspecified"))
      (node (ref "U15") (pin "7") (pinfunction "IO1_7") (pintype "bidirectional"))
      (node (ref "U2") (pin "14") (pinfunction "GPIO46_14") (pintype "bidirectional"))
    )
    (net (code "15") (name "IO2") (class "Default")
      (node (ref "CARD1") (pin "2") (pinfunction "CD/DAT3_2") (pintype "unspecified"))
      (node (ref "U15") (pin "9") (pinfunction "IO2_9") (pintype "bidirectional"))
      (node (ref "U2") (pin "17") (pinfunction "GPIO11_17") (pintype "bidirectional"))
    )
    (net (code "16") (name "IO3") (class "Default")
      (node (ref "CARD1") (pin "3") (pinfunction "CMD_3") (pintype "unspecified"))
      (node (ref "U15") (pin "10") (pinfunction "IO3_10") (pintype "bidirectional"))
      (node (ref "U2") (pin "18") (pinfunction "GPIO12_18") (pintype "bidirectional"))
    )
    (net (code "17") (name "IO4") (class "Default")
      (node (ref "CARD1") (pin "5") (pinfunction "CLK_5") (pintype "unspecified"))
      (node (ref "U15") (pin "11") (pinfunction "IO4_11") (pintype "bidirectional"))
      (node (ref "U2") (pin "19") (pinfunction "GPIO13_19") (pintype "bidirectional"))
    )
    (net (code "18") (name "IO5") (class "Default")
      (node (ref "CARD1") (pin "7") (pinfunction "DAT0_7") (pintype "unspecified"))
      (node (ref "U15") (pin "12") (pinfunction "IO5_12") (pintype "bidirectional"))
      (node (ref "U2") (pin "36") (pinfunction "GPIO00_36") (pintype "bidirectional"))
    )
    (net (code "19") (name "IO6") (class "Default")
      (node (ref "CARD1") (pin "8") (pinfunction "DAT1_8") (pintype "unspecified"))
      (node (ref "U15") (pin "13") (pinfunction "IO6_13") (pintype "bidirectional"))
      (node (ref "U2") (pin "37") (pinfunction "GPIO45_37") (pintype "input"))
    )
    (net (code "20") (name "IO7") (class "Default")
      (node (ref "CARD1") (pin "9") (pinfunction "CD_9") (pintype "unspecified"))
      (node (ref "U15") (pin "14") (pinfunction "IO7_14") (pintype "bidirectional"))
      (node (ref "U2") (pin "41") (pinfunction "GPIO20_41") (pintype "bidirectional"))
    )
    (net (code "21") (name "LED_RXD") (class "Default")
      (node (ref "R34") (pin "1") (pinfunction "1_1") (pintype "unspecified"))
      (node (ref "U12") (pin "6") (pinfunction "3Y_6") (pintype "unspecified"))
    )
    (net (code "22") (name "LED_TXD") (class "Default")
      (node (ref "R33") (pin "1") (pinfunction "1_1") (pintype "unspecified"))
      (node (ref "U12") (pin "11") (pinfunction "5A_11") (pintype "unspecified"))
      (node (ref "U12") (pin "2") (pinfunction "1Y_2") (pintype "unspecified"))
    )
    (net (code "23") (name "LTE_RX") (class "Default")
      (node (ref "J1") (pin "3") (pinfunction "2_3") (pintype "bidirectional"))
      (node (ref "U2") (pin "32") (pinfunction "GPIO38_32") (pintype "bidirectional"))
    )
    (net (code "24") (name "LTE_TX") (class "Default")
      (node (ref "J1") (pin "5") (pinfunction "3_5") (pintype "bidirectional"))
      (node (ref "U2") (pin "33") (pinfunction "GPIO37_33") (pintype "bidirectional"))
    )
    (net (code "25") (name "Net-(D10-A)") (class "Default")
      (node (ref "C4") (pin "1") (pinfunction "1_1") (pintype "unspecified"))
      (node (ref "D10") (pin "2") (pinfunction "A_2") (pintype "unspecified"))
      (node (ref "R32") (pin "1") (pinfunction "1_1") (pintype "input"))
      (node (ref "U12") (pin "13") (pinfunction "6A_13") (pintype "unspecified"))
    )
    (net (code "26") (name "Net-(D10-K)") (class "Default")
      (node (ref "D10") (pin "1") (pinfunction "K_1") (pintype "unspecified"))
      (node (ref "R32") (pin "2") (pinfunction "2_2") (pintype "input"))
      (node (ref "U11") (pin "4") (pinfunction "DI_4") (pintype "unspecified"))
      (node (ref "U12") (pin "10") (pinfunction "5Y_10") (pintype "unspecified"))
    )
    (net (code "27") (name "Net-(D12-Pad1)") (class "Default")
      (node (ref "D12") (pin "1") (pinfunction "1_1") (pintype "unspecified"))
      (node (ref "SW1") (pin "2") (pinfunction "2_2") (pintype "unspecified"))
      (node (ref "SW1") (pin "5") (pinfunction "5_5") (pintype "unspecified"))
    )
    (net (code "28") (name "Net-(PWR-K)") (class "Default")
      (node (ref "PWR") (pin "1") (pinfunction "K_1") (pintype "unspecified"))
      (node (ref "R36") (pin "1") (pinfunction "1_1") (pintype "unspecified"))
    )
    (net (code "29") (name "Net-(R11-Pad2)") (class "Default")
      (node (ref "R11") (pin "2") (pinfunction "2_2") (pintype "unspecified"))
      (node (ref "U3") (pin "3") (pinfunction "3_3") (pintype "unspecified"))
    )
    (net (code "30") (name "Net-(R12-Pad2)") (class "Default")
      (node (ref "R12") (pin "2") (pinfunction "2_2") (pintype "unspecified"))
      (node (ref "U3") (pin "1") (pinfunction "1_1") (pintype "unspecified"))
    )
    (net (code "31") (name "Net-(R13-Pad1)") (class "Default")
      (node (ref "R13") (pin "1") (pinfunction "1_1") (pintype "unspecified"))
      (node (ref "R15") (pin "1") (pinfunction "1_1") (pintype "unspecified"))
      (node (ref "U3") (pin "7") (pinfunction "7_7") (pintype "unspecified"))
    )
    (net (code "32") (name "Net-(R14-Pad1)") (class "Default")
      (node (ref "R14") (pin "1") (pinfunction "1_1") (pintype "unspecified"))
      (node (ref "R16") (pin "1") (pinfunction "1_1") (pintype "unspecified"))
      (node (ref "U3") (pin "5") (pinfunction "5_5") (pintype "unspecified"))
    )
    (net (code "33") (name "Net-(R19-Pad2)") (class "Default")
      (node (ref "R19") (pin "2") (pinfunction "2_2") (pintype "unspecified"))
      (node (ref "U7") (pin "3") (pinfunction "3_3") (pintype "unspecified"))
    )
    (net (code "34") (name "Net-(R20-Pad2)") (class "Default")
      (node (ref "R20") (pin "2") (pinfunction "2_2") (pintype "unspecified"))
      (node (ref "U7") (pin "1") (pinfunction "1_1") (pintype "unspecified"))
    )
    (net (code "35") (name "Net-(R21-Pad1)") (class "Default")
      (node (ref "R21") (pin "1") (pinfunction "1_1") (pintype "unspecified"))
      (node (ref "R23") (pin "1") (pinfunction "1_1") (pintype "unspecified"))
      (node (ref "U7") (pin "7") (pinfunction "7_7") (pintype "unspecified"))
    )
    (net (code "36") (name "Net-(R22-Pad1)") (class "Default")
      (node (ref "R22") (pin "1") (pinfunction "1_1") (pintype "unspecified"))
      (node (ref "R24") (pin "1") (pinfunction "1_1") (pintype "unspecified"))
      (node (ref "U7") (pin "5") (pinfunction "5_5") (pintype "unspecified"))
    )
    (net (code "37") (name "Net-(RRX-A)") (class "Default")
      (node (ref "R34") (pin "2") (pinfunction "2_2") (pintype "unspecified"))
      (node (ref "RRX") (pin "1") (pinfunction "A_1") (pintype "input"))
    )
    (net (code "38") (name "Net-(RTX-+)") (class "Default")
      (node (ref "R33") (pin "2") (pinfunction "2_2") (pintype "unspecified"))
      (node (ref "RTX") (pin "2") (pinfunction "+_2") (pintype "input"))
    )
    (net (code "39") (name "Net-(U1-VOUT)") (class "Default")
      (node (ref "R5") (pin "2") (pinfunction "2_2") (pintype "unspecified"))
      (node (ref "U1") (pin "2") (pinfunction "VOUT_2") (pintype "unspecified"))
    )
    (net (code "40") (name "Net-(U2-RST)") (class "Default")
      (node (ref "R8") (pin "2") (pinfunction "2_2") (pintype "input"))
      (node (ref "U2") (pin "3") (pinfunction "RST_3") (pintype "bidirectional"))
    )
    (net (code "41") (name "Net-(U5-BAK)") (class "Default")
      (node (ref "R16") (pin "2") (pinfunction "2_2") (pintype "unspecified"))
      (node (ref "R17") (pin "2") (pinfunction "2_2") (pintype "input"))
      (node (ref "U5") (pin "7") (pinfunction "BAK_7") (pintype "unspecified"))
      (node (ref "U6") (pin "5") (pinfunction "GATE2_5") (pintype "unspecified"))
    )
    (net (code "42") (name "Net-(U5-FOR)") (class "Default")
      (node (ref "R15") (pin "2") (pinfunction "2_2") (pintype "unspecified"))
      (node (ref "R18") (pin "2") (pinfunction "2_2") (pintype "input"))
      (node (ref "U5") (pin "6") (pinfunction "FOR_6") (pintype "unspecified"))
      (node (ref "U6") (pin "2") (pinfunction "GATE1_2") (pintype "unspecified"))
    )
    (net (code "43") (name "Net-(U9-VDD1)") (class "Default")
      (node (ref "R27") (pin "2") (pinfunction "2_2") (pintype "unspecified"))
      (node (ref "U9") (pin "2") (pinfunction "VDD1_2") (pintype "unspecified"))
      (node (ref "U9") (pin "3") (pinfunction "VDD2_3") (pintype "unspecified"))
    )
    (net (code "44") (name "Net-(U10-GATE1)") (class "Default")
      (node (ref "R23") (pin "2") (pinfunction "2_2") (pintype "unspecified"))
      (node (ref "R26") (pin "2") (pinfunction "2_2") (pintype "input"))
      (node (ref "U10") (pin "2") (pinfunction "GATE1_2") (pintype "unspecified"))
      (node (ref "U9") (pin "6") (pinfunction "FOR_6") (pintype "unspecified"))
    )
    (net (code "45") (name "Net-(U10-GATE2)") (class "Default")
      (node (ref "R24") (pin "2") (pinfunction "2_2") (pintype "unspecified"))
      (node (ref "R25") (pin "2") (pinfunction "2_2") (pintype "input"))
      (node (ref "U10") (pin "5") (pinfunction "GATE2_5") (pintype "unspecified"))
      (node (ref "U9") (pin "7") (pinfunction "BAK_7") (pintype "unspecified"))
    )
    (net (code "46") (name "Net-(U11-DE)") (class "Default")
      (node (ref "U11") (pin "2") (pinfunction "RE#_2") (pintype "unspecified"))
      (node (ref "U11") (pin "3") (pinfunction "DE_3") (pintype "unspecified"))
      (node (ref "U12") (pin "12") (pinfunction "6Y_12") (pintype "unspecified"))
    )
    (net (code "47") (name "Net-(U11-RO)") (class "Default")
      (node (ref "R31") (pin "1") (pinfunction "1_1") (pintype "input"))
      (node (ref "U11") (pin "1") (pinfunction "RO_1") (pintype "unspecified"))
      (node (ref "U12") (pin "9") (pinfunction "4A_9") (pintype "unspecified"))
    )
    (net (code "48") (name "Net-(U12-2A)") (class "Default")
      (node (ref "U12") (pin "3") (pinfunction "2A_3") (pintype "unspecified"))
      (node (ref "U12") (pin "8") (pinfunction "4Y_8") (pintype "unspecified"))
    )
    (net (code "49") (name "OL_SCL") (class "Default")
      (node (ref "H7") (pin "3") (pinfunction "3_3") (pintype "unspecified"))
      (node (ref "R40") (pin "2") (pinfunction "2_2") (pintype "unspecified"))
      (node (ref "U2") (pin "27") (pinfunction "GPIO02_27") (pintype "bidirectional"))
    )
    (net (code "50") (name "OL_SDA") (class "Default")
      (node (ref "H7") (pin "4") (pinfunction "4_4") (pintype "unspecified"))
      (node (ref "R39") (pin "2") (pinfunction "2_2") (pintype "unspecified"))
      (node (ref "U2") (pin "26") (pinfunction "GPIO01_26") (pintype "bidirectional"))
    )
    (net (code "51") (name "PB0") (class "Default")
      (node (ref "H5") (pin "15") (pinfunction "15_15") (pintype "unspecified"))
      (node (ref "R41") (pin "1") (pinfunction "1_1") (pintype "input"))
      (node (ref "U2") (pin "10") (pinfunction "GPIO17_10") (pintype "bidirectional"))
    )
    (net (code "52") (name "PB1") (class "Default")
      (node (ref "H5") (pin "16") (pinfunction "16_16") (pintype "unspecified"))
      (node (ref "R42") (pin "1") (pinfunction "1_1") (pintype "input"))
      (node (ref "U2") (pin "16") (pinfunction "GPIO10_16") (pintype "bidirectional"))
    )
    (net (code "53") (name "RGB") (class "Default")
      (node (ref "H3") (pin "1") (pinfunction "1_1") (pintype "unspecified"))
      (node (ref "U2") (pin "11") (pinfunction "GPIO18_11") (pintype "bidirectional"))
    )
    (net (code "54") (name "RL1") (class "Default")
      (node (ref "H1") (pin "3") (pinfunction "3_3") (pintype "unspecified"))
      (node (ref "U6") (pin "6") (pinfunction "DRAIN1_6") (pintype "unspecified"))
    )
    (net (code "55") (name "RL2") (class "Default")
      (node (ref "H1") (pin "2") (pinfunction "2_2") (pintype "unspecified"))
      (node (ref "U6") (pin "3") (pinfunction "DRAIN2_3") (pintype "unspecified"))
    )
    (net (code "56") (name "RL3") (class "Default")
      (node (ref "H1") (pin "14") (pinfunction "14_14") (pintype "unspecified"))
      (node (ref "U10") (pin "6") (pinfunction "DRAIN1_6") (pintype "unspecified"))
    )
    (net (code "57") (name "RL4") (class "Default")
      (node (ref "H1") (pin "13") (pinfunction "13_13") (pintype "unspecified"))
      (node (ref "U10") (pin "3") (pinfunction "DRAIN2_3") (pintype "unspecified"))
    )
    (net (code "58") (name "RS_RXD") (class "Default")
      (node (ref "H5") (pin "18") (pinfunction "18_18") (pintype "unspecified"))
      (node (ref "U12") (pin "4") (pinfunction "2Y_4") (pintype "unspecified"))
      (node (ref "U12") (pin "5") (pinfunction "3A_5") (pintype "unspecified"))
      (node (ref "U2") (pin "13") (pinfunction "GPIO03_13") (pintype "bidirectional"))
    )
    (net (code "59") (name "RS_TXD") (class "Default")
      (node (ref "H5") (pin "19") (pinfunction "19_19") (pintype "unspecified"))
      (node (ref "R35") (pin "1") (pinfunction "1_1") (pintype "input"))
      (node (ref "U12") (pin "1") (pinfunction "1A_1") (pintype "unspecified"))
      (node (ref "U2") (pin "12") (pinfunction "GPIO08_12") (pintype "bidirectional"))
    )
    (net (code "60") (name "S1B_P") (class "Default")
      (node (ref "H1") (pin "5") (pinfunction "5_5") (pintype "unspecified"))
      (node (ref "U5") (pin "1") (pinfunction "X4_1") (pintype "unspecified"))
    )
    (net (code "61") (name "S1F_N") (class "Default")
      (node (ref "H1") (pin "4") (pinfunction "4_4") (pintype "unspecified"))
      (node (ref "U5") (pin "4") (pinfunction "X3_4") (pintype "unspecified"))
    )
    (net (code "62") (name "S2B_P") (class "Default")
      (node (ref "H1") (pin "15") (pinfunction "15_15") (pintype "unspecified"))
      (node (ref "U9") (pin "1") (pinfunction "X4_1") (pintype "unspecified"))
    )
    (net (code "63") (name "S2F_N") (class "Default")
      (node (ref "H1") (pin "16") (pinfunction "16_16") (pintype "unspecified"))
      (node (ref "U9") (pin "4") (pinfunction "X3_4") (pintype "unspecified"))
    )
    (net (code "64") (name "SCL") (class "Default")
      (node (ref "U15") (pin "1") (pinfunction "SCL_1") (pintype "unspecified"))
      (node (ref "U19") (pin "1") (pinfunction "SCL_1") (pintype "unspecified"))
      (node (ref "U2") (pin "25") (pinfunction "GPIO44_25") (pintype "bidirectional"))
    )
    (net (code "65") (name "SDA") (class "Default")
      (node (ref "U15") (pin "2") (pinfunction "SDA_2") (pintype "bidirectional"))
      (node (ref "U19") (pin "16") (pinfunction "SDA_16") (pintype "unspecified"))
      (node (ref "U2") (pin "24") (pinfunction "GPIO43_24") (pintype "bidirectional"))
    )
    (net (code "66") (name "SENSE_3V3") (class "Default")
      (node (ref "H7") (pin "2") (pinfunction "2_2") (pintype "unspecified"))
      (node (ref "R39") (pin "1") (pinfunction "1_1") (pintype "unspecified"))
      (node (ref "R40") (pin "1") (pinfunction "1_1") (pintype "unspecified"))
    )
    (net (code "67") (name "SENSE_5V") (class "Default")
      (node (ref "C3") (pin "2") (pinfunction "2_2") (pintype "unspecified"))
      (node (ref "C6") (pin "1") (pinfunction "1_1") (pintype "input"))
      (node (ref "H5") (pin "1") (pinfunction "1_1") (pintype "unspecified"))
      (node (ref "H5") (pin "17") (pinfunction "17_17") (pintype "unspecified"))
      (node (ref "H5") (pin "5") (pinfunction "5_5") (pintype "unspecified"))
      (node (ref "H6") (pin "1") (pinfunction "1_1") (pintype "unspecified"))
      (node (ref "J1") (pin "2") (pinfunction "6_2") (pintype "bidirectional"))
      (node (ref "R29") (pin "2") (pinfunction "2_2") (pintype "input"))
      (node (ref "R31") (pin "2") (pinfunction "2_2") (pintype "input"))
      (node (ref "R35") (pin "2") (pinfunction "2_2") (pintype "input"))
      (node (ref "U1") (pin "1") (pinfunction "+VS_1") (pintype "unspecified"))
      (node (ref "U11") (pin "8") (pinfunction "VCC_8") (pintype "unspecified"))
      (node (ref "U12") (pin "14") (pinfunction "VCC_14") (pintype "unspecified"))
      (node (ref "U13") (pin "1") (pinfunction "OUT_1") (pintype "unspecified"))
    )
    (net (code "68") (name "SENSE_5V_EN") (class "Default")
      (node (ref "U13") (pin "4") (pinfunction "EN_4") (pintype "unspecified"))
      (node (ref "U2") (pin "38") (pinfunction "GPIO34_38") (pintype "bidirectional"))
    )
    (net (code "69") (name "SLR1_N") (class "Default")
      (node (ref "H1") (pin "8") (pinfunction "8_8") (pintype "unspecified"))
      (node (ref "R11") (pin "1") (pinfunction "1_1") (pintype "unspecified"))
      (node (ref "U2") (pin "34") (pinfunction "GPIO36_34") (pintype "bidirectional"))
    )
    (net (code "70") (name "SLR1_P") (class "Default")
      (node (ref "H1") (pin "9") (pinfunction "9_9") (pintype "unspecified"))
      (node (ref "R12") (pin "1") (pinfunction "1_1") (pintype "unspecified"))
      (node (ref "U2") (pin "35") (pinfunction "GPIO35_35") (pintype "bidirectional"))
    )
    (net (code "71") (name "SLR2_N") (class "Default")
      (node (ref "H1") (pin "18") (pinfunction "18_18") (pintype "unspecified"))
      (node (ref "R19") (pin "1") (pinfunction "1_1") (pintype "unspecified"))
      (node (ref "U2") (pin "40") (pinfunction "GPIO21_40") (pintype "bidirectional"))
    )
    (net (code "72") (name "SLR2_P") (class "Default")
      (node (ref "H1") (pin "19") (pinfunction "19_19") (pintype "unspecified"))
      (node (ref "R20") (pin "1") (pinfunction "1_1") (pintype "unspecified"))
      (node (ref "U2") (pin "39") (pinfunction "GPIO33_39") (pintype "bidirectional"))
    )
    (net (code "73") (name "SLR_5V") (class "Default")
      (node (ref "C1") (pin "2") (pinfunction "2_2") (pintype "unspecified"))
      (node (ref "C2") (pin "2") (pinfunction "2_2") (pintype "unspecified"))
      (node (ref "C7") (pin "1") (pinfunction "1_1") (pintype "input"))
      (node (ref "H1") (pin "1") (pinfunction "1_1") (pintype "unspecified"))
      (node (ref "H1") (pin "11") (pinfunction "11_11") (pintype "unspecified"))
      (node (ref "H1") (pin "17") (pinfunction "17_17") (pintype "unspecified"))
      (node (ref "H1") (pin "7") (pinfunction "7_7") (pintype "unspecified"))
      (node (ref "R27") (pin "1") (pinfunction "1_1") (pintype "unspecified"))
      (node (ref "U14") (pin "1") (pinfunction "OUT_1") (pintype "unspecified"))
      (node (ref "U3") (pin "6") (pinfunction "6_6") (pintype "unspecified"))
      (node (ref "U3") (pin "8") (pinfunction "8_8") (pintype "unspecified"))
      (node (ref "U4") (pin "1") (pinfunction "1_1") (pintype "unspecified"))
      (node (ref "U5") (pin "2") (pinfunction "VDD1_2") (pintype "unspecified"))
      (node (ref "U5") (pin "3") (pinfunction "VDD2_3") (pintype "unspecified"))
      (node (ref "U7") (pin "6") (pinfunction "6_6") (pintype "unspecified"))
      (node (ref "U7") (pin "8") (pinfunction "8_8") (pintype "unspecified"))
      (node (ref "U8") (pin "1") (pinfunction "1_1") (pintype "unspecified"))
    )
    (net (code "74") (name "SLR_5V_EN") (class "Default")
      (node (ref "U14") (pin "4") (pinfunction "EN_4") (pintype "unspecified"))
      (node (ref "U2") (pin "15") (pinfunction "GPIO09_15") (pintype "bidirectional"))
    )
    (net (code "75") (name "SN1LED") (class "Default")
      (node (ref "H2") (pin "2") (pinfunction "2_2") (pintype "input"))
      (node (ref "R14") (pin "2") (pinfunction "2_2") (pintype "unspecified"))
      (node (ref "SR2") (pin "2") (pinfunction "+_2") (pintype "input"))
    )
    (net (code "76") (name "SN2LED") (class "Default")
      (node (ref "H3") (pin "3") (pinfunction "3_3") (pintype "unspecified"))
      (node (ref "R22") (pin "2") (pinfunction "2_2") (pintype "unspecified"))
      (node (ref "SR4") (pin "2") (pinfunction "+_2") (pintype "input"))
    )
    (net (code "77") (name "SP1LED") (class "Default")
      (node (ref "H2") (pin "1") (pinfunction "1_1") (pintype "input"))
      (node (ref "R13") (pin "2") (pinfunction "2_2") (pintype "unspecified"))
      (node (ref "SR1") (pin "1") (pinfunction "A_1") (pintype "input"))
    )
    (net (code "78") (name "SP2LED") (class "Default")
      (node (ref "H3") (pin "2") (pinfunction "2_2") (pintype "unspecified"))
      (node (ref "R21") (pin "2") (pinfunction "2_2") (pintype "unspecified"))
      (node (ref "SR3") (pin "1") (pinfunction "A_1") (pintype "input"))
    )
    (net (code "79") (name "VB") (class "Default")
      (node (ref "R37") (pin "2") (pinfunction "2_2") (pintype "unspecified"))
      (node (ref "R38") (pin "1") (pinfunction "1_1") (pintype "unspecified"))
      (node (ref "U2") (pin "9") (pinfunction "GPIO16_9") (pintype "bidirectional"))
    )
    (net (code "80") (name "VI-1") (class "Default")
      (node (ref "H5") (pin "3") (pinfunction "3_3") (pintype "unspecified"))
      (node (ref "R1") (pin "1") (pinfunction "1_1") (pintype "unspecified"))
    )
    (net (code "81") (name "VI-2") (class "Default")
      (node (ref "H5") (pin "4") (pinfunction "4_4") (pintype "unspecified"))
      (node (ref "R3") (pin "1") (pinfunction "1_1") (pintype "unspecified"))
    )
    (net (code "82") (name "VI-3") (class "Default")
      (node (ref "H5") (pin "7") (pinfunction "7_7") (pintype "unspecified"))
      (node (ref "R7") (pin "1") (pinfunction "1_1") (pintype "unspecified"))
    )
    (net (code "83") (name "VI-4") (class "Default")
      (node (ref "H5") (pin "8") (pinfunction "8_8") (pintype "unspecified"))
      (node (ref "R9") (pin "1") (pinfunction "1_1") (pintype "unspecified"))
    )
    (net (code "84") (name "VIN+5V") (class "Default")
      (node (ref "CN1") (pin "1") (pinfunction "1_1") (pintype "input"))
      (node (ref "D11") (pin "2") (pinfunction "2_2") (pintype "unspecified"))
      (node (ref "D12") (pin "2") (pinfunction "2_2") (pintype "unspecified"))
    )
    (net (code "85") (name "VIN1") (class "Default")
      (node (ref "D1") (pin "1") (pinfunction "1_1") (pintype "unspecified"))
      (node (ref "R1") (pin "2") (pinfunction "2_2") (pintype "unspecified"))
      (node (ref "R2") (pin "1") (pinfunction "1_1") (pintype "unspecified"))
      (node (ref "U2") (pin "4") (pinfunction "GPIO04_4") (pintype "bidirectional"))
    )
    (net (code "86") (name "VIN2") (class "Default")
      (node (ref "D2") (pin "1") (pinfunction "1_1") (pintype "unspecified"))
      (node (ref "R3") (pin "2") (pinfunction "2_2") (pintype "unspecified"))
      (node (ref "R4") (pin "1") (pinfunction "1_1") (pintype "unspecified"))
      (node (ref "U2") (pin "5") (pinfunction "GPIO05_5") (pintype "bidirectional"))
    )
    (net (code "87") (name "VIN3") (class "Default")
      (node (ref "D3") (pin "1") (pinfunction "1_1") (pintype "unspecified"))
      (node (ref "R6") (pin "1") (pinfunction "1_1") (pintype "unspecified"))
      (node (ref "R7") (pin "2") (pinfunction "2_2") (pintype "unspecified"))
      (node (ref "U2") (pin "6") (pinfunction "GPIO06_6") (pintype "bidirectional"))
    )
    (net (code "88") (name "VIN4") (class "Default")
      (node (ref "D4") (pin "1") (pinfunction "1_1") (pintype "unspecified"))
      (node (ref "R10") (pin "1") (pinfunction "1_1") (pintype "unspecified"))
      (node (ref "R9") (pin "2") (pinfunction "2_2") (pintype "unspecified"))
      (node (ref "U2") (pin "7") (pinfunction "GPIO07_7") (pintype "bidirectional"))
    )
    (net (code "89") (name "VT") (class "Default")
      (node (ref "R5") (pin "1") (pinfunction "1_1") (pintype "unspecified"))
      (node (ref "U2") (pin "8") (pinfunction "GPIO15_8") (pintype "bidirectional"))
    )
    (net (code "90") (name "unconnected-(J1-4-Pad6)") (class "Default")
      (node (ref "J1") (pin "6") (pinfunction "4_6") (pintype "bidirectional+no_connect"))
    )
    (net (code "91") (name "unconnected-(J1-5-Pad4)") (class "Default")
      (node (ref "J1") (pin "4") (pinfunction "5_4") (pintype "bidirectional+no_connect"))
    )
    (net (code "92") (name "unconnected-(LDO1-GND-Pad1)") (class "Default")
      (node (ref "LDO1") (pin "1") (pinfunction "GND_1") (pintype "unspecified"))
    )
    (net (code "93") (name "unconnected-(LDO1-VDD-Pad3)") (class "Default")
      (node (ref "LDO1") (pin "3") (pinfunction "VDD_3") (pintype "unspecified"))
    )
    (net (code "94") (name "unconnected-(LDO1-VOUT-Pad2)") (class "Default")
      (node (ref "LDO1") (pin "2") (pinfunction "VOUT_2") (pintype "unspecified"))
    )
    (net (code "95") (name "unconnected-(SW1-Pad0)") (class "Default")
      (node (ref "SW1") (pin "0") (pinfunction "0_0") (pintype "unspecified+no_connect"))
    )
    (net (code "96") (name "unconnected-(SW1-Pad0)_1") (class "Default")
      (node (ref "SW1") (pin "0") (pinfunction "0_0") (pintype "unspecified+no_connect"))
    )
    (net (code "97") (name "unconnected-(SW1-Pad1)") (class "Default")
      (node (ref "SW1") (pin "1") (pinfunction "1_1") (pintype "unspecified+no_connect"))
    )
    (net (code "98") (name "unconnected-(SW1-Pad6)") (class "Default")
      (node (ref "SW1") (pin "6") (pinfunction "6_6") (pintype "unspecified+no_connect"))
    )
    (net (code "99") (name "unconnected-(U13-FLT#-Pad3)") (class "Default")
      (node (ref "U13") (pin "3") (pinfunction "FLT#_3") (pintype "unspecified+no_connect"))
    )
    (net (code "100") (name "unconnected-(U14-FLT#-Pad3)") (class "Default")
      (node (ref "U14") (pin "3") (pinfunction "FLT#_3") (pintype "unspecified+no_connect"))
    )
    (net (code "101") (name "unconnected-(U15-A0-Pad3)") (class "Default")
      (node (ref "U15") (pin "3") (pinfunction "A0_3") (pintype "unspecified+no_connect"))
    )
    (net (code "102") (name "unconnected-(U15-A1-Pad4)") (class "Default")
      (node (ref "U15") (pin "4") (pinfunction "A1_4") (pintype "unspecified+no_connect"))
    )
    (net (code "103") (name "unconnected-(U15-A2-Pad5)") (class "Default")
      (node (ref "U15") (pin "5") (pinfunction "A2_5") (pintype "unspecified+no_connect"))
    )
    (net (code "104") (name "unconnected-(U16-Pad1)") (class "Default")
      (node (ref "U16") (pin "1") (pinfunction "1_1") (pintype "unspecified"))
    )
    (net (code "105") (name "unconnected-(U16-Pad2)") (class "Default")
      (node (ref "U16") (pin "2") (pinfunction "2_2") (pintype "unspecified"))
    )
    (net (code "106") (name "unconnected-(U16-Pad3)") (class "Default")
      (node (ref "U16") (pin "3") (pinfunction "3_3") (pintype "unspecified"))
    )
    (net (code "107") (name "unconnected-(U16-Pad4)") (class "Default")
      (node (ref "U16") (pin "4") (pinfunction "4_4") (pintype "unspecified"))
    )
    (net (code "108") (name "unconnected-(U16-Pad5)") (class "Default")
      (node (ref "U16") (pin "5") (pinfunction "5_5") (pintype "unspecified"))
    )
    (net (code "109") (name "unconnected-(U16-Pad6)") (class "Default")
      (node (ref "U16") (pin "6") (pinfunction "6_6") (pintype "unspecified"))
    )
    (net (code "110") (name "unconnected-(U16-Pad7)") (class "Default")
      (node (ref "U16") (pin "7") (pinfunction "7_7") (pintype "unspecified"))
    )
    (net (code "111") (name "unconnected-(U16-Pad8)") (class "Default")
      (node (ref "U16") (pin "8") (pinfunction "8_8") (pintype "unspecified"))
    )
    (net (code "112") (name "unconnected-(U16-Pad9)") (class "Default")
      (node (ref "U16") (pin "9") (pinfunction "9_9") (pintype "unspecified"))
    )
    (net (code "113") (name "unconnected-(U16-Pad10)") (class "Default")
      (node (ref "U16") (pin "10") (pinfunction "10_10") (pintype "unspecified"))
    )
    (net (code "114") (name "unconnected-(U16-Pad11)") (class "Default")
      (node (ref "U16") (pin "11") (pinfunction "11_11") (pintype "unspecified"))
    )
    (net (code "115") (name "unconnected-(U16-Pad12)") (class "Default")
      (node (ref "U16") (pin "12") (pinfunction "12_12") (pintype "unspecified"))
    )
    (net (code "116") (name "unconnected-(U16-Pad13)") (class "Default")
      (node (ref "U16") (pin "13") (pinfunction "13_13") (pintype "unspecified"))
    )
    (net (code "117") (name "unconnected-(U16-Pad14)") (class "Default")
      (node (ref "U16") (pin "14") (pinfunction "14_14") (pintype "unspecified"))
    )
    (net (code "118") (name "unconnected-(U16-Pad15)") (class "Default")
      (node (ref "U16") (pin "15") (pinfunction "15_15") (pintype "unspecified"))
    )
    (net (code "119") (name "unconnected-(U16-Pad16)") (class "Default")
      (node (ref "U16") (pin "16") (pinfunction "16_16") (pintype "unspecified"))
    )
    (net (code "120") (name "unconnected-(U16-Pad17)") (class "Default")
      (node (ref "U16") (pin "17") (pinfunction "17_17") (pintype "unspecified"))
    )
    (net (code "121") (name "unconnected-(U16-Pad18)") (class "Default")
      (node (ref "U16") (pin "18") (pinfunction "18_18") (pintype "unspecified"))
    )
    (net (code "122") (name "unconnected-(U16-Pad19)") (class "Default")
      (node (ref "U16") (pin "19") (pinfunction "19_19") (pintype "unspecified"))
    )
    (net (code "123") (name "unconnected-(U16-Pad20)") (class "Default")
      (node (ref "U16") (pin "20") (pinfunction "20_20") (pintype "unspecified"))
    )
    (net (code "124") (name "unconnected-(U16-Pad21)") (class "Default")
      (node (ref "U16") (pin "21") (pinfunction "21_21") (pintype "unspecified"))
    )
    (net (code "125") (name "unconnected-(U16-Pad22)") (class "Default")
      (node (ref "U16") (pin "22") (pinfunction "22_22") (pintype "unspecified"))
    )
    (net (code "126") (name "unconnected-(U16-Pad23)") (class "Default")
      (node (ref "U16") (pin "23") (pinfunction "23_23") (pintype "unspecified"))
    )
    (net (code "127") (name "unconnected-(U16-Pad24)") (class "Default")
      (node (ref "U16") (pin "24") (pinfunction "24_24") (pintype "unspecified"))
    )
    (net (code "128") (name "unconnected-(U16-Pad25)") (class "Default")
      (node (ref "U16") (pin "25") (pinfunction "25_25") (pintype "unspecified"))
    )
    (net (code "129") (name "unconnected-(U16-Pad26)") (class "Default")
      (node (ref "U16") (pin "26") (pinfunction "26_26") (pintype "unspecified"))
    )
    (net (code "130") (name "unconnected-(U16-Pad27)") (class "Default")
      (node (ref "U16") (pin "27") (pinfunction "27_27") (pintype "unspecified"))
    )
    (net (code "131") (name "unconnected-(U16-Pad28)") (class "Default")
      (node (ref "U16") (pin "28") (pinfunction "28_28") (pintype "unspecified"))
    )
    (net (code "132") (name "unconnected-(U16-Pad29)") (class "Default")
      (node (ref "U16") (pin "29") (pinfunction "29_29") (pintype "unspecified"))
    )
    (net (code "133") (name "unconnected-(U16-Pad30)") (class "Default")
      (node (ref "U16") (pin "30") (pinfunction "30_30") (pintype "unspecified"))
    )
    (net (code "134") (name "unconnected-(U16-Pad31)") (class "Default")
      (node (ref "U16") (pin "31") (pinfunction "31_31") (pintype "unspecified"))
    )
    (net (code "135") (name "unconnected-(U16-Pad32)") (class "Default")
      (node (ref "U16") (pin "32") (pinfunction "32_32") (pintype "unspecified"))
    )
    (net (code "136") (name "unconnected-(U16-Pad33)") (class "Default")
      (node (ref "U16") (pin "33") (pinfunction "33_33") (pintype "unspecified"))
    )
    (net (code "137") (name "unconnected-(U16-Pad34)") (class "Default")
      (node (ref "U16") (pin "34") (pinfunction "34_34") (pintype "unspecified"))
    )
    (net (code "138") (name "unconnected-(U16-Pad35)") (class "Default")
      (node (ref "U16") (pin "35") (pinfunction "35_35") (pintype "unspecified"))
    )
    (net (code "139") (name "unconnected-(U16-Pad36)") (class "Default")
      (node (ref "U16") (pin "36") (pinfunction "36_36") (pintype "unspecified"))
    )
    (net (code "140") (name "unconnected-(U16-Pad37)") (class "Default")
      (node (ref "U16") (pin "37") (pinfunction "37_37") (pintype "unspecified"))
    )
    (net (code "141") (name "unconnected-(U16-Pad38)") (class "Default")
      (node (ref "U16") (pin "38") (pinfunction "38_38") (pintype "unspecified"))
    )
    (net (code "142") (name "unconnected-(U16-Pad39)") (class "Default")
      (node (ref "U16") (pin "39") (pinfunction "39_39") (pintype "unspecified"))
    )
    (net (code "143") (name "unconnected-(U16-Pad40)") (class "Default")
      (node (ref "U16") (pin "40") (pinfunction "40_40") (pintype "unspecified"))
    )
    (net (code "144") (name "unconnected-(U17-Pad1)") (class "Default")
      (node (ref "U17") (pin "1") (pinfunction "1_1") (pintype "unspecified"))
    )
    (net (code "145") (name "unconnected-(U17-Pad2)") (class "Default")
      (node (ref "U17") (pin "2") (pinfunction "2_2") (pintype "unspecified"))
    )
    (net (code "146") (name "unconnected-(U17-Pad3)") (class "Default")
      (node (ref "U17") (pin "3") (pinfunction "3_3") (pintype "unspecified"))
    )
    (net (code "147") (name "unconnected-(U17-Pad4)") (class "Default")
      (node (ref "U17") (pin "4") (pinfunction "4_4") (pintype "unspecified"))
    )
    (net (code "148") (name "unconnected-(U17-Pad5)") (class "Default")
      (node (ref "U17") (pin "5") (pinfunction "5_5") (pintype "unspecified"))
    )
    (net (code "149") (name "unconnected-(U17-Pad6)") (class "Default")
      (node (ref "U17") (pin "6") (pinfunction "6_6") (pintype "unspecified"))
    )
    (net (code "150") (name "unconnected-(U17-Pad7)") (class "Default")
      (node (ref "U17") (pin "7") (pinfunction "7_7") (pintype "unspecified"))
    )
    (net (code "151") (name "unconnected-(U17-Pad8)") (class "Default")
      (node (ref "U17") (pin "8") (pinfunction "8_8") (pintype "unspecified"))
    )
    (net (code "152") (name "unconnected-(U17-Pad9)") (class "Default")
      (node (ref "U17") (pin "9") (pinfunction "9_9") (pintype "unspecified"))
    )
    (net (code "153") (name "unconnected-(U17-Pad10)") (class "Default")
      (node (ref "U17") (pin "10") (pinfunction "10_10") (pintype "unspecified"))
    )
    (net (code "154") (name "unconnected-(U17-Pad11)") (class "Default")
      (node (ref "U17") (pin "11") (pinfunction "11_11") (pintype "unspecified"))
    )
    (net (code "155") (name "unconnected-(U17-Pad12)") (class "Default")
      (node (ref "U17") (pin "12") (pinfunction "12_12") (pintype "unspecified"))
    )
    (net (code "156") (name "unconnected-(U17-Pad13)") (class "Default")
      (node (ref "U17") (pin "13") (pinfunction "13_13") (pintype "unspecified"))
    )
    (net (code "157") (name "unconnected-(U17-Pad14)") (class "Default")
      (node (ref "U17") (pin "14") (pinfunction "14_14") (pintype "unspecified"))
    )
    (net (code "158") (name "unconnected-(U17-Pad15)") (class "Default")
      (node (ref "U17") (pin "15") (pinfunction "15_15") (pintype "unspecified"))
    )
    (net (code "159") (name "unconnected-(U17-Pad16)") (class "Default")
      (node (ref "U17") (pin "16") (pinfunction "16_16") (pintype "unspecified"))
    )
    (net (code "160") (name "unconnected-(U17-Pad17)") (class "Default")
      (node (ref "U17") (pin "17") (pinfunction "17_17") (pintype "unspecified"))
    )
    (net (code "161") (name "unconnected-(U17-Pad18)") (class "Default")
      (node (ref "U17") (pin "18") (pinfunction "18_18") (pintype "unspecified"))
    )
    (net (code "162") (name "unconnected-(U17-Pad19)") (class "Default")
      (node (ref "U17") (pin "19") (pinfunction "19_19") (pintype "unspecified"))
    )
    (net (code "163") (name "unconnected-(U17-Pad20)") (class "Default")
      (node (ref "U17") (pin "20") (pinfunction "20_20") (pintype "unspecified"))
    )
    (net (code "164") (name "unconnected-(U17-Pad21)") (class "Default")
      (node (ref "U17") (pin "21") (pinfunction "21_21") (pintype "unspecified"))
    )
    (net (code "165") (name "unconnected-(U17-Pad22)") (class "Default")
      (node (ref "U17") (pin "22") (pinfunction "22_22") (pintype "unspecified"))
    )
    (net (code "166") (name "unconnected-(U17-Pad23)") (class "Default")
      (node (ref "U17") (pin "23") (pinfunction "23_23") (pintype "unspecified"))
    )
    (net (code "167") (name "unconnected-(U17-Pad24)") (class "Default")
      (node (ref "U17") (pin "24") (pinfunction "24_24") (pintype "unspecified"))
    )
    (net (code "168") (name "unconnected-(U17-Pad25)") (class "Default")
      (node (ref "U17") (pin "25") (pinfunction "25_25") (pintype "unspecified"))
    )
    (net (code "169") (name "unconnected-(U17-Pad26)") (class "Default")
      (node (ref "U17") (pin "26") (pinfunction "26_26") (pintype "unspecified"))
    )
    (net (code "170") (name "unconnected-(U17-Pad27)") (class "Default")
      (node (ref "U17") (pin "27") (pinfunction "27_27") (pintype "unspecified"))
    )
    (net (code "171") (name "unconnected-(U17-Pad28)") (class "Default")
      (node (ref "U17") (pin "28") (pinfunction "28_28") (pintype "unspecified"))
    )
    (net (code "172") (name "unconnected-(U17-Pad29)") (class "Default")
      (node (ref "U17") (pin "29") (pinfunction "29_29") (pintype "unspecified"))
    )
    (net (code "173") (name "unconnected-(U17-Pad30)") (class "Default")
      (node (ref "U17") (pin "30") (pinfunction "30_30") (pintype "unspecified"))
    )
    (net (code "174") (name "unconnected-(U17-Pad31)") (class "Default")
      (node (ref "U17") (pin "31") (pinfunction "31_31") (pintype "unspecified"))
    )
    (net (code "175") (name "unconnected-(U17-Pad32)") (class "Default")
      (node (ref "U17") (pin "32") (pinfunction "32_32") (pintype "unspecified"))
    )
    (net (code "176") (name "unconnected-(U17-Pad33)") (class "Default")
      (node (ref "U17") (pin "33") (pinfunction "33_33") (pintype "unspecified"))
    )
    (net (code "177") (name "unconnected-(U17-Pad34)") (class "Default")
      (node (ref "U17") (pin "34") (pinfunction "34_34") (pintype "unspecified"))
    )
    (net (code "178") (name "unconnected-(U17-Pad35)") (class "Default")
      (node (ref "U17") (pin "35") (pinfunction "35_35") (pintype "unspecified"))
    )
    (net (code "179") (name "unconnected-(U17-Pad36)") (class "Default")
      (node (ref "U17") (pin "36") (pinfunction "36_36") (pintype "unspecified"))
    )
    (net (code "180") (name "unconnected-(U17-Pad37)") (class "Default")
      (node (ref "U17") (pin "37") (pinfunction "37_37") (pintype "unspecified"))
    )
    (net (code "181") (name "unconnected-(U17-Pad38)") (class "Default")
      (node (ref "U17") (pin "38") (pinfunction "38_38") (pintype "unspecified"))
    )
    (net (code "182") (name "unconnected-(U17-Pad39)") (class "Default")
      (node (ref "U17") (pin "39") (pinfunction "39_39") (pintype "unspecified"))
    )
    (net (code "183") (name "unconnected-(U17-Pad40)") (class "Default")
      (node (ref "U17") (pin "40") (pinfunction "40_40") (pintype "unspecified"))
    )
    (net (code "184") (name "unconnected-(U19-C1-Pad10)") (class "Default")
      (node (ref "U19") (pin "10") (pinfunction "C1_10") (pintype "unspecified+no_connect"))
    )
    (net (code "185") (name "unconnected-(U19-NC-Pad3)") (class "Default")
      (node (ref "U19") (pin "3") (pinfunction "NC_3") (pintype "unspecified+no_connect"))
    )
    (net (code "186") (name "unconnected-(U19-NC-Pad5)") (class "Default")
      (node (ref "U19") (pin "5") (pinfunction "NC_5") (pintype "unspecified+no_connect"))
    )
    (net (code "187") (name "unconnected-(U19-NC-Pad6)") (class "Default")
      (node (ref "U19") (pin "6") (pinfunction "NC_6") (pintype "unspecified+no_connect"))
    )
    (net (code "188") (name "unconnected-(U19-NC-Pad7)") (class "Default")
      (node (ref "U19") (pin "7") (pinfunction "NC_7") (pintype "unspecified+no_connect"))
    )
    (net (code "189") (name "unconnected-(U19-NC-Pad14)") (class "Default")
      (node (ref "U19") (pin "14") (pinfunction "NC_14") (pintype "unspecified+no_connect"))
    )
    (net (code "190") (name "unconnected-(U19-S1-Pad4)") (class "Default")
      (node (ref "U19") (pin "4") (pinfunction "S1_4") (pintype "unspecified+no_connect"))
    )
  )
)
